# Outlet.net
KiCad netlist of a schematic drawn in EAGLE
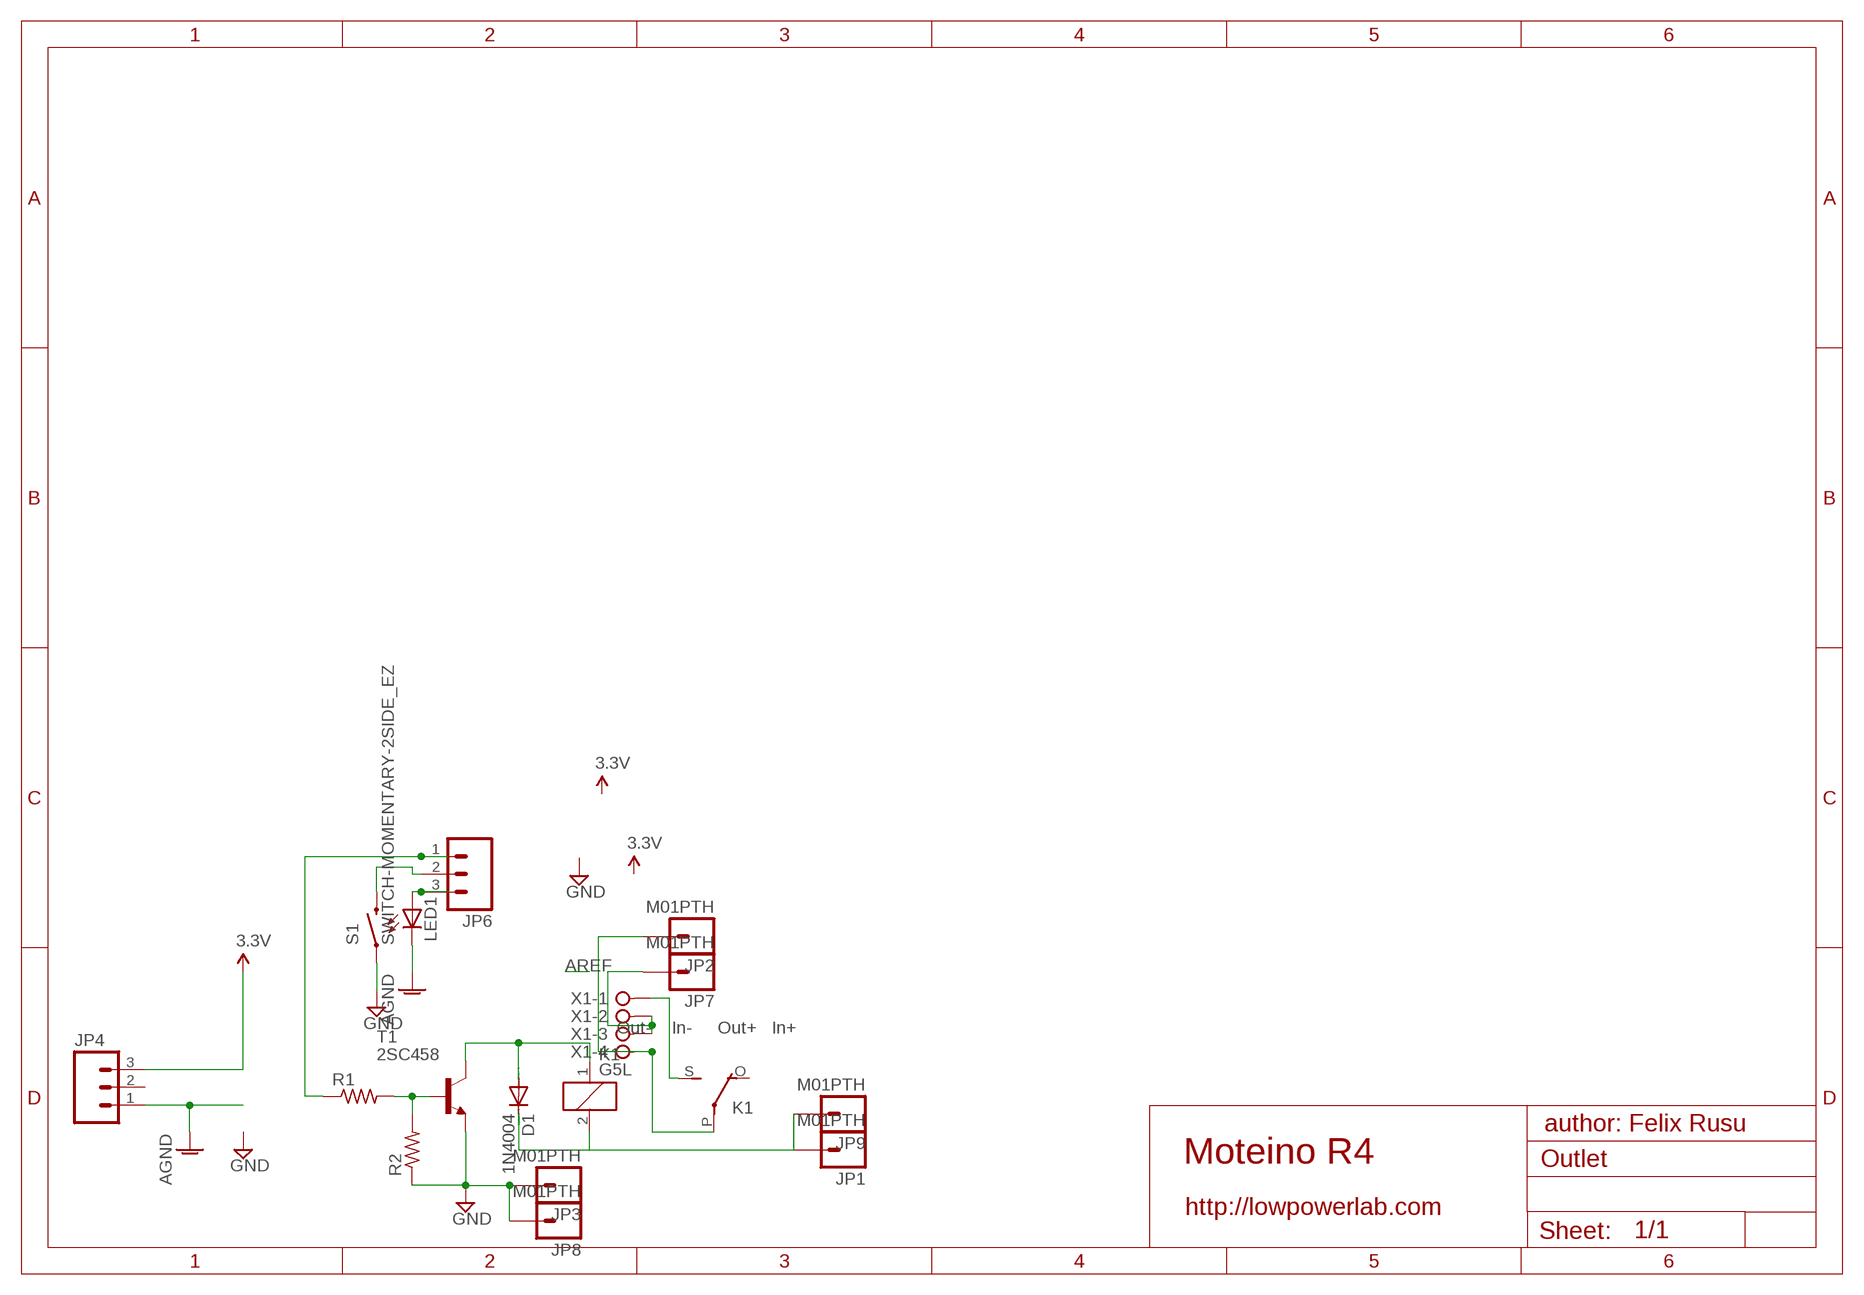
[diagram p0: schematic, sheet 1]

(export (version "E")
  (design (tool "Eeschema 10.0.6"))
  (components
    (comp (ref "D1")
      (value "1N4004")
      (footprint "eagle-import:DO41-10")
      (libsource (lib "eagle-import") (part "1N4004"))
    )
    (comp (ref "JP1")
      (value "M01PTH")
      (footprint "eagle-import:1X01")
      (libsource (lib "eagle-import") (part "M01PTH"))
    )
    (comp (ref "JP2")
      (value "M01PTH")
      (footprint "eagle-import:1X01")
      (libsource (lib "eagle-import") (part "M01PTH"))
    )
    (comp (ref "JP3")
      (value "M01PTH")
      (footprint "eagle-import:1X01")
      (libsource (lib "eagle-import") (part "M01PTH"))
    )
    (comp (ref "JP4")
      (value "M03PTH")
      (footprint "eagle-import:1X03")
      (libsource (lib "eagle-import") (part "M03PTH"))
    )
    (comp (ref "JP6")
      (value "M03PTH")
      (footprint "eagle-import:1X03")
      (libsource (lib "eagle-import") (part "M03PTH"))
    )
    (comp (ref "JP7")
      (value "M01PTH")
      (footprint "eagle-import:1X01")
      (libsource (lib "eagle-import") (part "M01PTH"))
    )
    (comp (ref "JP8")
      (value "M01PTH")
      (footprint "eagle-import:1X01")
      (libsource (lib "eagle-import") (part "M01PTH"))
    )
    (comp (ref "JP9")
      (value "M01PTH")
      (footprint "eagle-import:1X01")
      (libsource (lib "eagle-import") (part "M01PTH"))
    )
    (comp (ref "K1")
      (value "G5L")
      (footprint "eagle-import:G5LE")
      (libsource (lib "eagle-import") (part "G5L"))
    )
    (comp (ref "LED1")
      (value "LED3MM")
      (footprint "eagle-import:LED3MM")
      (libsource (lib "eagle-import") (part "LED3MM"))
    )
    (comp (ref "R1")
      (value "R-US_0204/7")
      (footprint "eagle-import:0204_7")
      (libsource (lib "eagle-import") (part "R-US_0204/7"))
    )
    (comp (ref "R2")
      (value "R-US_0204/7")
      (footprint "eagle-import:0204_7")
      (libsource (lib "eagle-import") (part "R-US_0204/7"))
    )
    (comp (ref "S1")
      (value "SWITCH-MOMENTARY-2SIDE_EZ")
      (footprint "eagle-import:TACTILE-PTH-SIDEEZ")
      (libsource (lib "eagle-import") (part "SWITCH-MOMENTARY-2SIDE_EZ"))
    )
    (comp (ref "T1")
      (value "2SC458")
      (footprint "eagle-import:TO92-ECB")
      (libsource (lib "eagle-import") (part "2SC458"))
    )
    (comp (ref "X1")
      (value "Out- In- Out+ In+")
      (footprint "eagle-import:W237-4P")
      (fields (field (name "MF") "In-") (field (name "MPN") "Out-"))
      (libsource (lib "eagle-import") (part "W237-04P"))
    )
  )
  (nets
    (net (code "2") (name "3.3V") (class "Default")
      (node (ref "JP4") (pin "3") (pinfunction "3_3") (pintype "passive"))
    )
    (net (code "3") (name "AGND") (class "Default")
      (node (ref "JP4") (pin "1") (pinfunction "1_1") (pintype "passive"))
      (node (ref "LED1") (pin "K") (pinfunction "C_K") (pintype "passive"))
    )
    (net (code "4") (name "GND") (class "Default")
      (node (ref "JP3") (pin "1") (pinfunction "1_1") (pintype "passive"))
      (node (ref "JP8") (pin "1") (pinfunction "1_1") (pintype "passive"))
      (node (ref "R2") (pin "1") (pinfunction "1_1") (pintype "passive"))
      (node (ref "S1") (pin "1") (pinfunction "1_1") (pintype "passive"))
      (node (ref "T1") (pin "E") (pinfunction "E_E") (pintype "passive"))
    )
    (net (code "5") (name "Net-(D1-PadA)") (class "Default")
      (node (ref "D1") (pin "A") (pinfunction "A_A") (pintype "passive"))
      (node (ref "K1") (pin "1") (pinfunction "1_1") (pintype "passive"))
      (node (ref "T1") (pin "C") (pinfunction "C_C") (pintype "passive"))
    )
    (net (code "6") (name "Net-(D1-PadC)") (class "Default")
      (node (ref "D1") (pin "C") (pinfunction "C_C") (pintype "passive"))
      (node (ref "JP1") (pin "1") (pinfunction "1_1") (pintype "passive"))
      (node (ref "JP9") (pin "1") (pinfunction "1_1") (pintype "passive"))
      (node (ref "K1") (pin "2") (pinfunction "2_2") (pintype "passive"))
    )
    (net (code "7") (name "Net-(JP6-Pad1)") (class "Default")
      (node (ref "JP6") (pin "1") (pinfunction "1_1") (pintype "passive"))
      (node (ref "R1") (pin "1") (pinfunction "1_1") (pintype "passive"))
    )
    (net (code "8") (name "Net-(JP6-Pad2)") (class "Default")
      (node (ref "JP6") (pin "2") (pinfunction "2_2") (pintype "passive"))
      (node (ref "S1") (pin "2") (pinfunction "2_2") (pintype "passive"))
    )
    (net (code "9") (name "Net-(JP6-Pad3)") (class "Default")
      (node (ref "JP6") (pin "3") (pinfunction "3_3") (pintype "passive"))
      (node (ref "LED1") (pin "A") (pinfunction "A_A") (pintype "passive"))
    )
    (net (code "10") (name "Net-(R1-Pad2)") (class "Default")
      (node (ref "R1") (pin "2") (pinfunction "2_2") (pintype "passive"))
      (node (ref "R2") (pin "2") (pinfunction "2_2") (pintype "passive"))
      (node (ref "T1") (pin "B") (pinfunction "B_B") (pintype "passive"))
    )
    (net (code "11") (name "Net-(X1A-KL)") (class "Default")
      (node (ref "K1") (pin "S") (pinfunction "S_S") (pintype "passive"))
      (node (ref "X1") (pin "1") (pinfunction "KL_1") (pintype "passive"))
    )
    (net (code "12") (name "Net-(X1B-KL)") (class "Default")
      (node (ref "JP7") (pin "1") (pinfunction "1_1") (pintype "passive"))
      (node (ref "X1") (pin "2") (pinfunction "KL_2") (pintype "passive"))
      (node (ref "X1") (pin "3") (pinfunction "KL_3") (pintype "passive"))
    )
    (net (code "13") (name "Net-(X1D-KL)") (class "Default")
      (node (ref "JP2") (pin "1") (pinfunction "1_1") (pintype "passive"))
      (node (ref "K1") (pin "P") (pinfunction "P_P") (pintype "passive"))
      (node (ref "X1") (pin "4") (pinfunction "KL_4") (pintype "passive"))
    )
    (net (code "14") (name "unconnected-(JP4-Pad2)") (class "Default")
      (node (ref "JP4") (pin "2") (pinfunction "2_2") (pintype "passive"))
    )
    (net (code "15") (name "unconnected-(K1-PadO)") (class "Default")
      (node (ref "K1") (pin "O") (pinfunction "O_O") (pintype "passive"))
    )
  )
)
